# DAC.net
KiCad netlist of a schematic drawn in Altium Designer
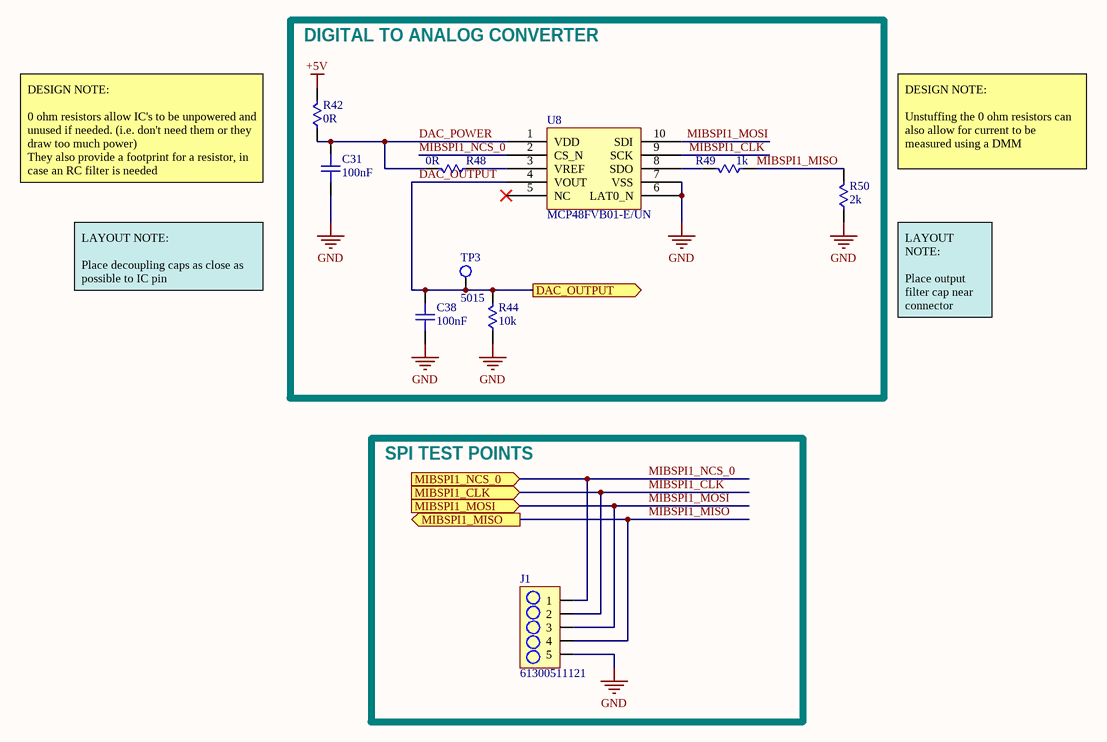
[diagram p0: DAC.SchDoc]

(export (version "E")
  (design (tool "Eeschema 10.0.6"))
  (components
    (comp (ref "C31")
      (value "100nF")
      (footprint "C0402")
      (description "CAP MLCC 0.1uF 10V X5R 0402 20% SMD 0402 85C Paper T/R")
      (fields
        (field (name "MANUFACTURER") "Samsung")
        (field (name "MANUFACTURER PART NUMBER") "CL05A104MP5NNNC")
      )
      (libsource (lib "PHANTOM_LIBRARY") (part "CL05A104MP5NNNC"))
    )
    (comp (ref "C38")
      (value "100nF")
      (footprint "C0402")
      (description "CAP MLCC 0.1uF 10V X5R 0402 20% SMD 0402 85C Paper T/R")
      (fields
        (field (name "MANUFACTURER") "Samsung")
        (field (name "MANUFACTURER PART NUMBER") "CL05A104MP5NNNC")
      )
      (libsource (lib "PHANTOM_LIBRARY") (part "CL05A104MP5NNNC"))
    )
    (comp (ref "J1")
      (value "61300511121")
      (footprint "5PIN_HEADER")
      (fields (field (name "MANUFACTURER") "Wurth Electronics"))
      (libsource (lib "PHANTOM_LIBRARY") (part "61300511121"))
    )
    (comp (ref "R42")
      (value "0R")
      (footprint "R0402")
      (description "RES SMD 0 OHM 1/16W 0402")
      (fields
        (field (name "MANUFACTURER") "Yageo")
        (field (name "MANUFACTURER PART NUMBER") "RC0402JR-070RL")
      )
      (libsource (lib "PHANTOM_LIBRARY") (part "RC0402JR-070RL"))
    )
    (comp (ref "R44")
      (value "10k")
      (footprint "R0402")
      (description "RES SMD 10K OHM 5% 1/16W 0402")
      (fields
        (field (name "MANUFACTURER") "Yageo")
        (field (name "MANUFACTURER PART NUMBER") "RC0402JR-0710KL")
      )
      (libsource (lib "PHANTOM_LIBRARY") (part "RC0402JR-0710KL"))
    )
    (comp (ref "R48")
      (value "0R")
      (footprint "R0402")
      (description "RES SMD 0 OHM 1/16W 0402")
      (fields
        (field (name "MANUFACTURER") "Yageo")
        (field (name "MANUFACTURER PART NUMBER") "RC0402JR-070RL")
      )
      (libsource (lib "PHANTOM_LIBRARY") (part "RC0402JR-070RL"))
    )
    (comp (ref "R49")
      (value "1k")
      (footprint "R0402")
      (description "RES SMD 1K OHM 0.5% 1/16W 0402")
      (fields
        (field (name "MANUFACTURER") "Susumu")
        (field (name "MANUFACTURER PART NUMBER") "RR0510P-102-D")
      )
      (libsource (lib "PHANTOM_LIBRARY") (part "RR0510P-102-D"))
    )
    (comp (ref "R50")
      (value "2k")
      (footprint "R0402")
      (description "RES SMD 2K OHM 1% 1/16W 0402")
      (fields
        (field (name "MANUFACTURER") "Yageo")
        (field (name "MANUFACTURER PART NUMBER") "RC0402FR-072KL")
      )
      (libsource (lib "PHANTOM_LIBRARY") (part "RC0402FR-072KL"))
    )
    (comp (ref "TP3")
      (value "5015")
      (footprint "TP_HOOK")
      (description "TEST POINT, PCB, SMT")
      (fields (field (name "MANUFACTURER") "Keystone Electronics"))
      (libsource (lib "PHANTOM_LIBRARY") (part "5015"))
    )
    (comp (ref "U8")
      (value "MCP48FVB01-E/UN")
      (footprint "MSSOP-10")
      (description "IC DAC 8BIT V-OUT BUFF 10-MSOP")
      (fields (field (name "MANUFACTURER") "Microchip"))
      (libsource (lib "PHANTOM_LIBRARY") (part "MCP48FVB01-E/UN"))
    )
  )
  (nets
    (net (code "1") (name "+5V") (class "Default")
      (node (ref "R42") (pin "2") (pinfunction "2_2") (pintype "passive"))
    )
    (net (code "2") (name "/DAC_OUTPUT") (class "Default")
      (node (ref "C38") (pin "2") (pinfunction "2_2") (pintype "passive"))
      (node (ref "R44") (pin "2") (pinfunction "2_2") (pintype "passive"))
      (node (ref "TP3") (pin "1") (pinfunction "1_1") (pintype "passive"))
      (node (ref "U8") (pin "4") (pinfunction "VOUT_4") (pintype "passive"))
    )
    (net (code "3") (name "/DAC_POWER") (class "Default")
      (node (ref "C31") (pin "2") (pinfunction "2_2") (pintype "passive"))
      (node (ref "R42") (pin "1") (pinfunction "1_1") (pintype "passive"))
      (node (ref "R48") (pin "2") (pinfunction "2_2") (pintype "passive"))
      (node (ref "U8") (pin "1") (pinfunction "VDD_1") (pintype "passive"))
    )
    (net (code "4") (name "/MIBSPI1_CLK") (class "Default")
      (node (ref "J1") (pin "2") (pinfunction "2_2") (pintype "passive"))
      (node (ref "U8") (pin "9") (pinfunction "SCK_9") (pintype "passive"))
    )
    (net (code "5") (name "/MIBSPI1_MISO") (class "Default")
      (node (ref "J1") (pin "4") (pinfunction "4_4") (pintype "passive"))
      (node (ref "R49") (pin "1") (pinfunction "1_1") (pintype "passive"))
      (node (ref "R50") (pin "2") (pinfunction "2_2") (pintype "passive"))
    )
    (net (code "6") (name "/MIBSPI1_MOSI") (class "Default")
      (node (ref "J1") (pin "3") (pinfunction "3_3") (pintype "passive"))
      (node (ref "U8") (pin "10") (pinfunction "SDI_10") (pintype "passive"))
    )
    (net (code "7") (name "/MIBSPI1_NCS_0") (class "Default")
      (node (ref "J1") (pin "1") (pinfunction "1_1") (pintype "passive"))
      (node (ref "U8") (pin "2") (pinfunction "CS_N_2") (pintype "passive"))
    )
    (net (code "8") (name "GND") (class "Default")
      (node (ref "C31") (pin "1") (pinfunction "1_1") (pintype "passive"))
      (node (ref "C38") (pin "1") (pinfunction "1_1") (pintype "passive"))
      (node (ref "J1") (pin "5") (pinfunction "5_5") (pintype "passive"))
      (node (ref "R44") (pin "1") (pinfunction "1_1") (pintype "passive"))
      (node (ref "R50") (pin "1") (pinfunction "1_1") (pintype "passive"))
      (node (ref "U8") (pin "6") (pinfunction "LAT0_N_6") (pintype "passive"))
      (node (ref "U8") (pin "7") (pinfunction "VSS_7") (pintype "passive"))
    )
    (net (code "9") (name "Net-(U8-SDO)") (class "Default")
      (node (ref "R49") (pin "2") (pinfunction "2_2") (pintype "passive"))
      (node (ref "U8") (pin "8") (pinfunction "SDO_8") (pintype "passive"))
    )
    (net (code "10") (name "Net-(U8-VREF)") (class "Default")
      (node (ref "R48") (pin "1") (pinfunction "1_1") (pintype "passive"))
      (node (ref "U8") (pin "3") (pinfunction "VREF_3") (pintype "passive"))
    )
    (net (code "11") (name "unconnected-(U8-NC-Pad5)") (class "Default")
      (node (ref "U8") (pin "5") (pinfunction "NC_5") (pintype "passive+no_connect"))
    )
  )
)
